# mod_switch_battery_voltage.net
KiCad netlist of a schematic drawn in EAGLE
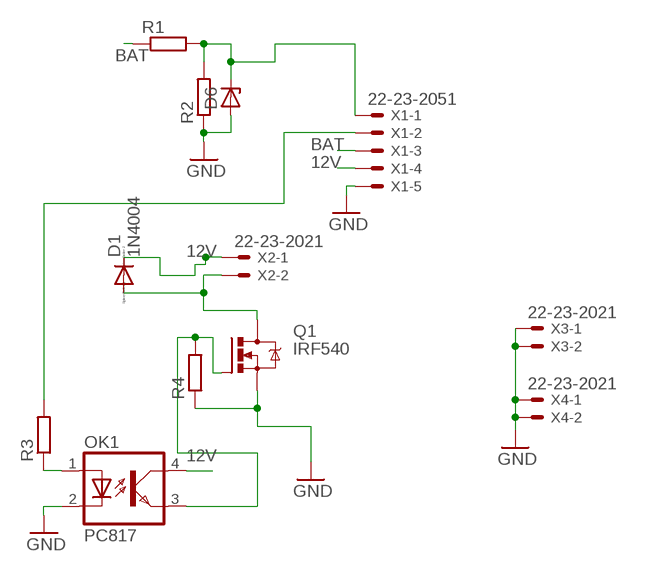
[diagram p0: schematic, sheet 1]

(export (version "E")
  (design (tool "Eeschema 10.0.6"))
  (components
    (comp (ref "D1")
      (value "1N4004")
      (footprint "eagle-import:DO41-10")
      (libsource (lib "eagle-import") (part "1N4004"))
    )
    (comp (ref "D6")
      (value "ZENER-DIODEDO34-7")
      (footprint "eagle-import:DO34Z7")
      (libsource (lib "eagle-import") (part "ZENER-DIODEDO34-7"))
    )
    (comp (ref "OK1")
      (value "PC817")
      (footprint "eagle-import:DIL04")
      (fields (field (name "MPN") "PC817X4J000F"))
      (libsource (lib "eagle-import") (part "PC817"))
    )
    (comp (ref "Q1")
      (value "IRF540")
      (footprint "eagle-import:TO220BV")
      (libsource (lib "eagle-import") (part "IRF540"))
    )
    (comp (ref "R1")
      (value "R-EU_0204/5")
      (footprint "eagle-import:0204_5")
      (libsource (lib "eagle-import") (part "R-EU_0204/5"))
    )
    (comp (ref "R2")
      (value "R-EU_0204/5")
      (footprint "eagle-import:0204_5")
      (libsource (lib "eagle-import") (part "R-EU_0204/5"))
    )
    (comp (ref "R3")
      (value "R-EU_0204/5")
      (footprint "eagle-import:0204_5")
      (libsource (lib "eagle-import") (part "R-EU_0204/5"))
    )
    (comp (ref "R4")
      (value "R-EU_0204/5")
      (footprint "eagle-import:0204_5")
      (libsource (lib "eagle-import") (part "R-EU_0204/5"))
    )
    (comp (ref "X1")
      (value "22-23-2051")
      (footprint "eagle-import:22-23-2051")
      (fields (field (name "MF") "MOLEX"))
      (libsource (lib "eagle-import") (part "22-23-2051"))
    )
    (comp (ref "X2")
      (value "22-23-2021")
      (footprint "eagle-import:22-23-2021")
      (fields (field (name "MF") "MOLEX"))
      (libsource (lib "eagle-import") (part "22-23-2021"))
    )
    (comp (ref "X3")
      (value "22-23-2021")
      (footprint "eagle-import:22-23-2021")
      (fields (field (name "MF") "MOLEX"))
      (libsource (lib "eagle-import") (part "22-23-2021"))
    )
    (comp (ref "X4")
      (value "22-23-2021")
      (footprint "eagle-import:22-23-2021")
      (fields (field (name "MF") "MOLEX"))
      (libsource (lib "eagle-import") (part "22-23-2021"))
    )
  )
  (nets
    (net (code "1") (name "/12V") (class "Default")
      (node (ref "D1") (pin "C") (pinfunction "C_C") (pintype "passive"))
      (node (ref "OK1") (pin "4") (pinfunction "COL_4") (pintype "passive"))
      (node (ref "X1") (pin "4") (pinfunction "S_4") (pintype "passive"))
      (node (ref "X2") (pin "1") (pinfunction "S_1") (pintype "passive"))
    )
    (net (code "2") (name "/BAT") (class "Default")
      (node (ref "R1") (pin "1") (pinfunction "1_1") (pintype "passive"))
      (node (ref "X1") (pin "3") (pinfunction "S_3") (pintype "passive"))
    )
    (net (code "3") (name "GND") (class "Default")
      (node (ref "D6") (pin "A") (pinfunction "A_A") (pintype "passive"))
      (node (ref "OK1") (pin "2") (pinfunction "C_2") (pintype "passive"))
      (node (ref "Q1") (pin "S") (pinfunction "S_S") (pintype "passive"))
      (node (ref "R2") (pin "1") (pinfunction "1_1") (pintype "passive"))
      (node (ref "R4") (pin "1") (pinfunction "1_1") (pintype "passive"))
      (node (ref "X1") (pin "5") (pinfunction "S_5") (pintype "passive"))
      (node (ref "X3") (pin "1") (pinfunction "S_1") (pintype "passive"))
      (node (ref "X3") (pin "2") (pinfunction "S_2") (pintype "passive"))
      (node (ref "X4") (pin "1") (pinfunction "S_1") (pintype "passive"))
      (node (ref "X4") (pin "2") (pinfunction "S_2") (pintype "passive"))
    )
    (net (code "4") (name "Net-(OK1-A)") (class "Default")
      (node (ref "OK1") (pin "1") (pinfunction "A_1") (pintype "passive"))
      (node (ref "R3") (pin "1") (pinfunction "1_1") (pintype "passive"))
    )
    (net (code "5") (name "Net-(OK1-EMIT)") (class "Default")
      (node (ref "OK1") (pin "3") (pinfunction "EMIT_3") (pintype "passive"))
      (node (ref "Q1") (pin "G") (pinfunction "G_G") (pintype "passive"))
      (node (ref "R4") (pin "2") (pinfunction "2_2") (pintype "passive"))
    )
    (net (code "6") (name "Net-(X1A-S)") (class "Default")
      (node (ref "D6") (pin "C") (pinfunction "C_C") (pintype "passive"))
      (node (ref "R1") (pin "2") (pinfunction "2_2") (pintype "passive"))
      (node (ref "R2") (pin "2") (pinfunction "2_2") (pintype "passive"))
      (node (ref "X1") (pin "1") (pinfunction "S_1") (pintype "passive"))
    )
    (net (code "7") (name "Net-(X1B-S)") (class "Default")
      (node (ref "R3") (pin "2") (pinfunction "2_2") (pintype "passive"))
      (node (ref "X1") (pin "2") (pinfunction "S_2") (pintype "passive"))
    )
    (net (code "8") (name "Net-(X2B-S)") (class "Default")
      (node (ref "D1") (pin "A") (pinfunction "A_A") (pintype "passive"))
      (node (ref "Q1") (pin "D") (pinfunction "D_D") (pintype "passive"))
      (node (ref "X2") (pin "2") (pinfunction "S_2") (pintype "passive"))
    )
  )
)
